# 01_MAIN.net
KiCad netlist of a schematic drawn in Altium Designer
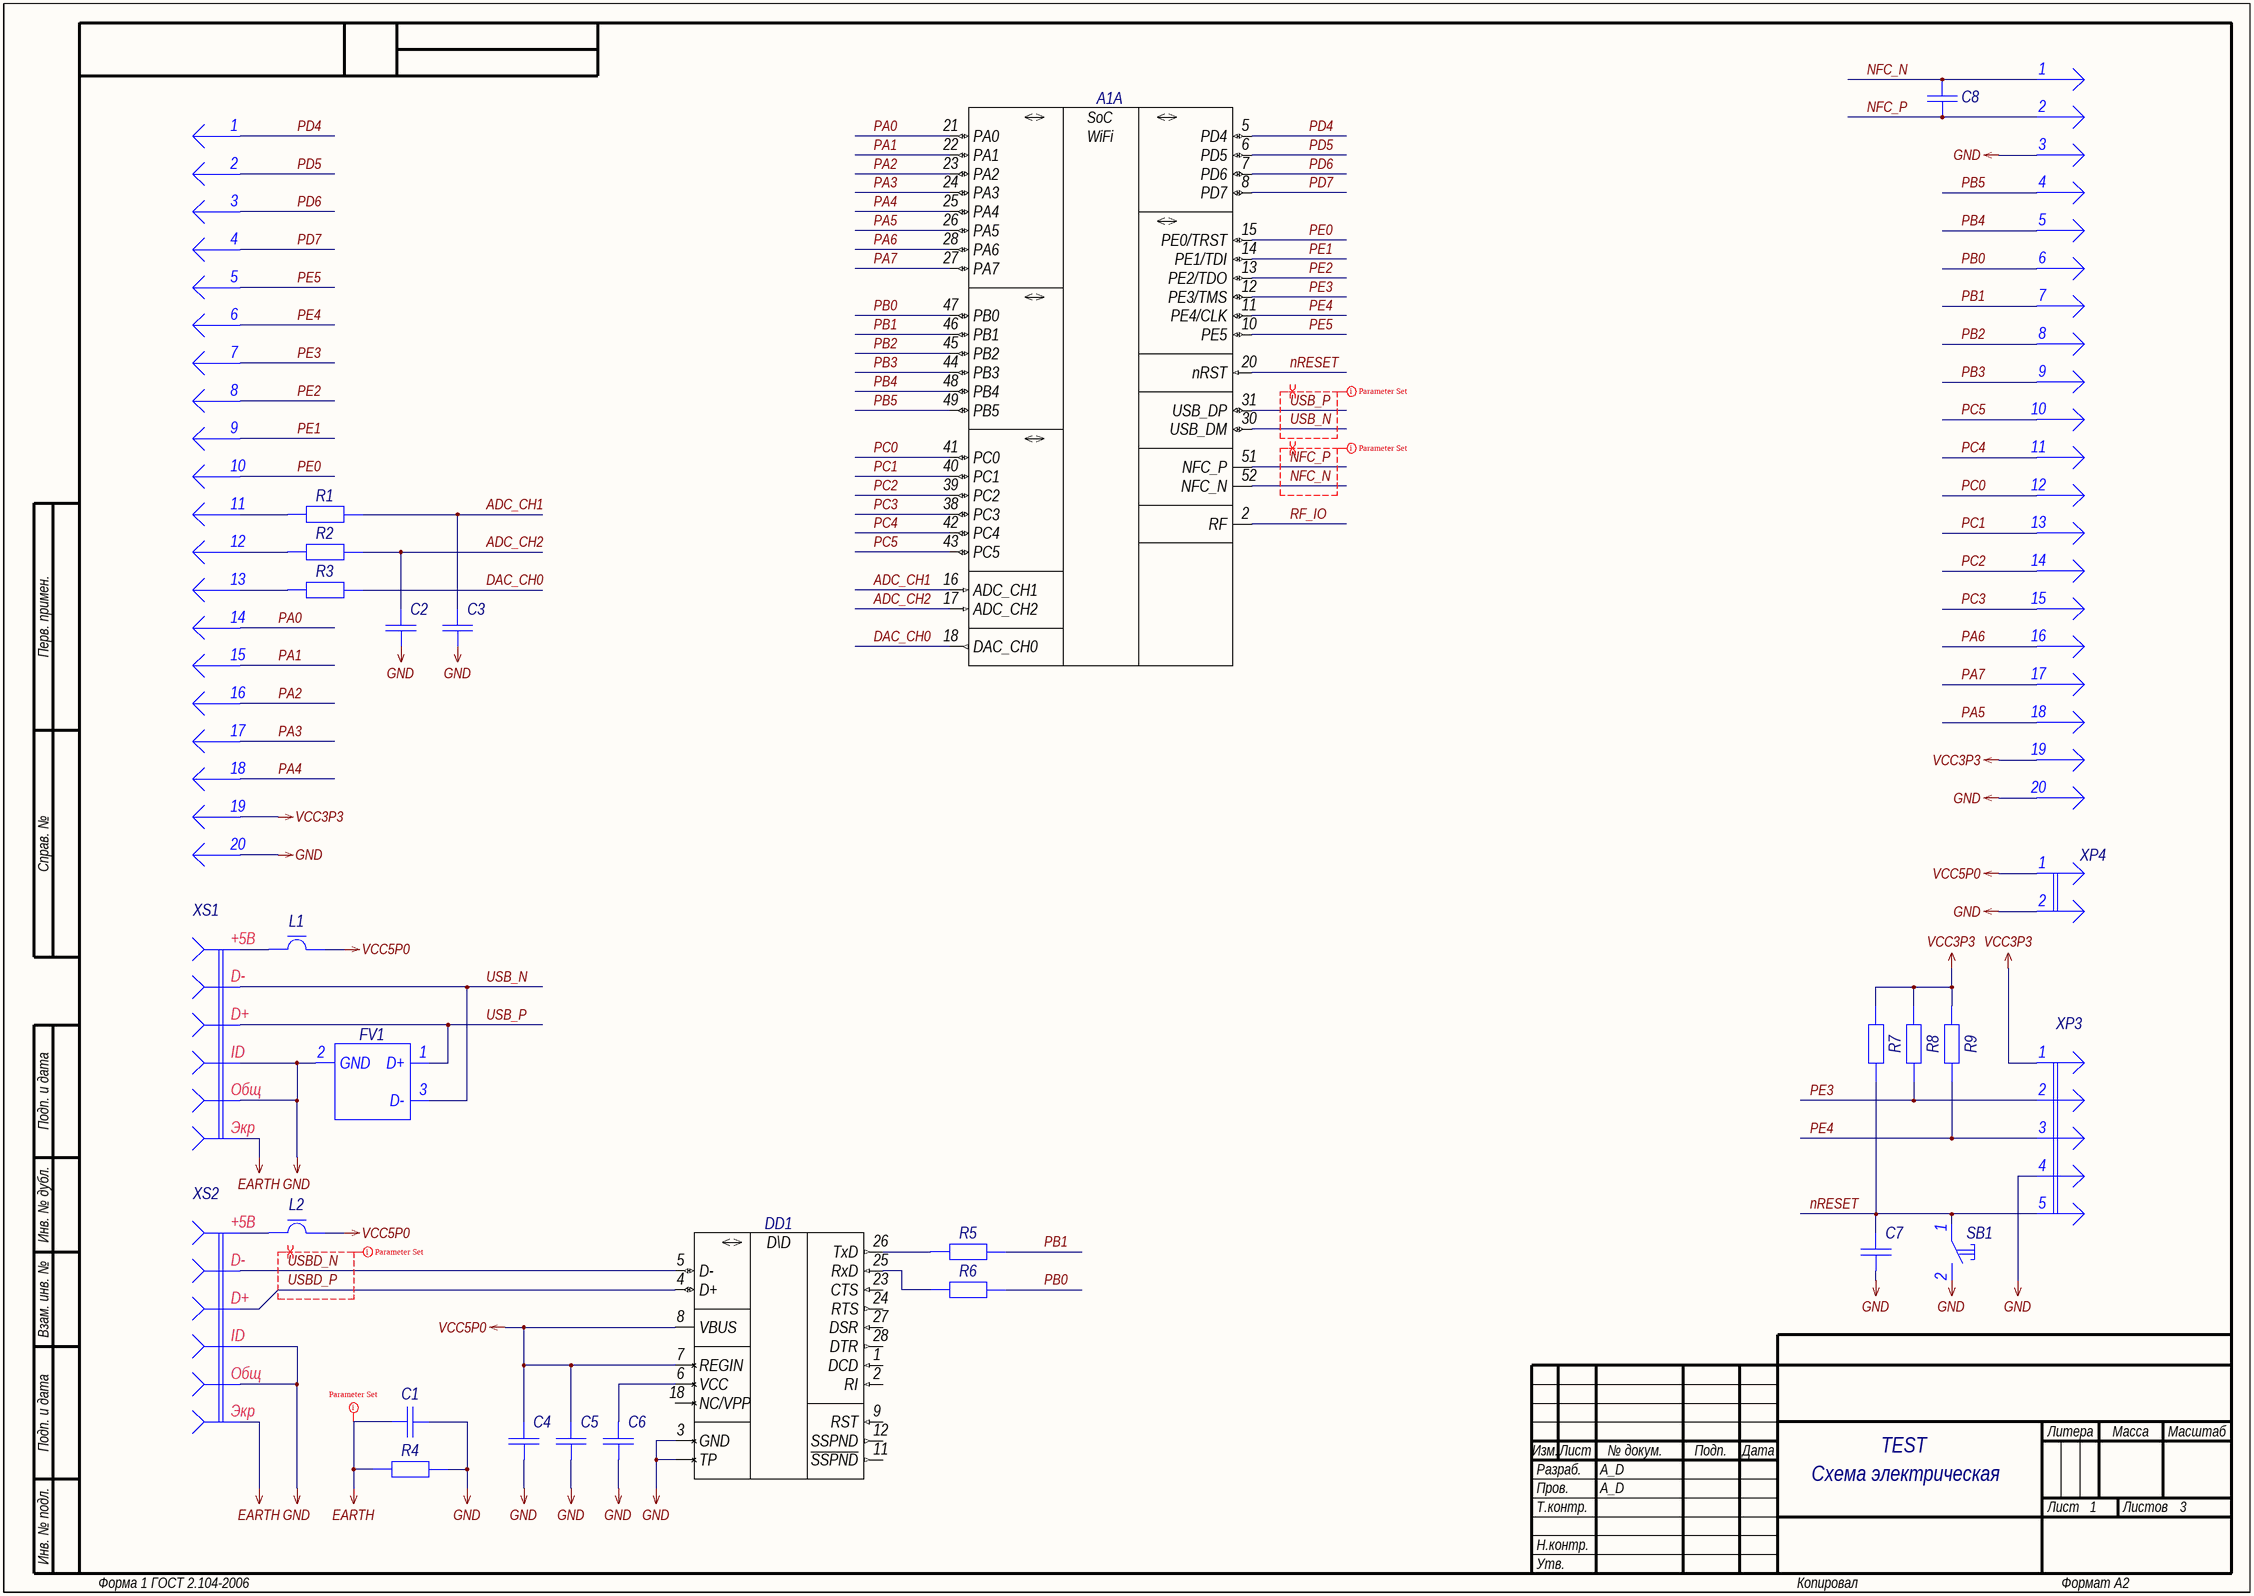
[diagram p0: 01_MAIN.SchDoc]

(export (version "E")
  (design (tool "Eeschema 10.0.6"))
  (components
    (comp (ref "A1")
      (value "AMB-02")
      (footprint "AMB-02")
      (fields
        (field (name "PART NUMBER") "MJIOT-AMB-02")
        (field (name "MANUFACTURER") "MJIOT")
        (field (name "PUBLISHER") "Andrew Danich")
      )
      (libsource (lib "ADLib") (part "AMB-02"))
    )
    (comp (ref "C1")
      (value "Capacitor")
      (footprint "C0603_L")
      (fields
        (field (name "PART NUMBER") "GRM188R72A104KA35D")
        (field (name "VOLTAGE") "100V")
        (field (name "TOLERANCE") "±10%")
        (field (name "PUBLISHER") "Andrew Danich")
      )
      (libsource (lib "ADLib") (part "Capacitor"))
    )
    (comp (ref "C2")
      (value "Capacitor")
      (footprint "C0603_L")
      (fields
        (field (name "PART NUMBER") "GCM1885C2A101JA16D")
        (field (name "VOLTAGE") "100V")
        (field (name "TOLERANCE") "±5%")
        (field (name "PUBLISHER") "Andrew Danich")
      )
      (libsource (lib "ADLib") (part "Capacitor"))
    )
    (comp (ref "C3")
      (value "Capacitor")
      (footprint "C0603_L")
      (fields
        (field (name "PART NUMBER") "GCM1885C2A101JA16D")
        (field (name "VOLTAGE") "100V")
        (field (name "TOLERANCE") "±5%")
        (field (name "PUBLISHER") "Andrew Danich")
      )
      (libsource (lib "ADLib") (part "Capacitor"))
    )
    (comp (ref "C4")
      (value "Capacitor")
      (footprint "C0603_L")
      (fields
        (field (name "PART NUMBER") "GCM188R71E105KA64D")
        (field (name "VOLTAGE") "25V")
        (field (name "TOLERANCE") "±10%")
        (field (name "PUBLISHER") "Andrew Danich")
      )
      (libsource (lib "ADLib") (part "Capacitor"))
    )
    (comp (ref "C5")
      (value "Capacitor")
      (footprint "C0603_L")
      (fields
        (field (name "PART NUMBER") "GRM188R72A104KA35D")
        (field (name "VOLTAGE") "100V")
        (field (name "TOLERANCE") "±10%")
        (field (name "PUBLISHER") "Andrew Danich")
      )
      (libsource (lib "ADLib") (part "Capacitor"))
    )
    (comp (ref "C6")
      (value "Capacitor")
      (footprint "C0603_L")
      (fields
        (field (name "PART NUMBER") "GRM188R72A104KA35D")
        (field (name "VOLTAGE") "100V")
        (field (name "TOLERANCE") "±10%")
        (field (name "PUBLISHER") "Andrew Danich")
      )
      (libsource (lib "ADLib") (part "Capacitor"))
    )
    (comp (ref "C7")
      (value "Capacitor")
      (footprint "C0603_L")
      (fields
        (field (name "PART NUMBER") "GRM188R72A104KA35D")
        (field (name "VOLTAGE") "100V")
        (field (name "TOLERANCE") "±10%")
        (field (name "PUBLISHER") "Andrew Danich")
      )
      (libsource (lib "ADLib") (part "Capacitor"))
    )
    (comp (ref "C8")
      (value "Capacitor")
      (footprint "C0603_L")
      (fields
        (field (name "PART NUMBER") "GRM1885C2A8R2DA01D")
        (field (name "VOLTAGE") "100V")
        (field (name "TOLERANCE") "±0.5pF")
        (field (name "PUBLISHER") "Andrew Danich")
      )
      (libsource (lib "ADLib") (part "Capacitor"))
    )
    (comp (ref "DD1")
      (value "CP2102_9")
      (footprint "QFN-28_050P500X500X100_N")
      (description "Single Chip USB to UART Bridge")
      (fields
        (field (name "PART NUMBER") "CP2102-GM")
        (field (name "MANUFACTURER") "Silicon Labs")
        (field (name "PUBLISHER") "Andrew Danich")
      )
      (libsource (lib "ADLib") (part "CP2102_9"))
    )
    (comp (ref "FV1")
      (value "TPD2EUSB30DRT")
      (footprint "SOT-3_070P100X080X050_N")
      (fields (field (name "MANUFACTURER") "Texas Instruments") (field (name "PUBLISHER") "Andrew Danich"))
      (libsource (lib "ADLib") (part "TPD2EUSB30DRT"))
    )
    (comp (ref "L1")
      (value "FerriteBead")
      (footprint "L0805_L")
      (fields
        (field (name "PART NUMBER") "BLM21PG331SN1")
        (field (name "MANUFACTURER") "Murata")
        (field (name "PUBLISHER") "Andrew Danich")
      )
      (libsource (lib "ADLib") (part "FerriteBead"))
    )
    (comp (ref "L2")
      (value "FerriteBead")
      (footprint "L0805_L")
      (fields
        (field (name "PART NUMBER") "BLM21PG331SN1")
        (field (name "MANUFACTURER") "Murata")
        (field (name "PUBLISHER") "Andrew Danich")
      )
      (libsource (lib "ADLib") (part "FerriteBead"))
    )
    (comp (ref "R1")
      (value "Resistor")
      (footprint "R0603_L")
      (fields
        (field (name "PART NUMBER") "RC0603JR-07100R")
        (field (name "TOLERANCE") "±5%")
        (field (name "MANUFACTURER") "Yageo")
        (field (name "PUBLISHER") "Andrew Danich")
      )
      (libsource (lib "ADLib") (part "Resistor"))
    )
    (comp (ref "R2")
      (value "Resistor")
      (footprint "R0603_L")
      (fields
        (field (name "PART NUMBER") "RC0603JR-07100R")
        (field (name "TOLERANCE") "±5%")
        (field (name "MANUFACTURER") "Yageo")
        (field (name "PUBLISHER") "Andrew Danich")
      )
      (libsource (lib "ADLib") (part "Resistor"))
    )
    (comp (ref "R3")
      (value "Resistor")
      (footprint "R0603_L")
      (fields
        (field (name "PART NUMBER") "RC0603JR-070R")
        (field (name "TOLERANCE") "±5%")
        (field (name "MANUFACTURER") "Yageo")
        (field (name "PUBLISHER") "Andrew Danich")
      )
      (libsource (lib "ADLib") (part "Resistor"))
    )
    (comp (ref "R4")
      (value "Resistor")
      (footprint "R0603_L")
      (fields
        (field (name "PART NUMBER") "RC0603JR-07100KL")
        (field (name "TOLERANCE") "±5%")
        (field (name "MANUFACTURER") "Yageo")
        (field (name "PUBLISHER") "Andrew Danich")
      )
      (libsource (lib "ADLib") (part "Resistor"))
    )
    (comp (ref "R5")
      (value "Resistor")
      (footprint "R0603_L")
      (fields
        (field (name "PART NUMBER") "RC0603JR-071KL")
        (field (name "TOLERANCE") "±5%")
        (field (name "MANUFACTURER") "Yageo")
        (field (name "PUBLISHER") "Andrew Danich")
      )
      (libsource (lib "ADLib") (part "Resistor"))
    )
    (comp (ref "R6")
      (value "Resistor")
      (footprint "R0603_L")
      (fields
        (field (name "PART NUMBER") "RC0603JR-071KL")
        (field (name "TOLERANCE") "±5%")
        (field (name "MANUFACTURER") "Yageo")
        (field (name "PUBLISHER") "Andrew Danich")
      )
      (libsource (lib "ADLib") (part "Resistor"))
    )
    (comp (ref "R7")
      (value "Resistor")
      (footprint "R0603_L")
      (fields
        (field (name "PART NUMBER") "RC0603JR-0710KL")
        (field (name "TOLERANCE") "±5%")
        (field (name "MANUFACTURER") "Yageo")
        (field (name "PUBLISHER") "Andrew Danich")
      )
      (libsource (lib "ADLib") (part "Resistor"))
    )
    (comp (ref "R8")
      (value "Resistor")
      (footprint "R0603_L")
      (fields
        (field (name "PART NUMBER") "RC0603JR-0710KL")
        (field (name "TOLERANCE") "±5%")
        (field (name "MANUFACTURER") "Yageo")
        (field (name "PUBLISHER") "Andrew Danich")
      )
      (libsource (lib "ADLib") (part "Resistor"))
    )
    (comp (ref "R9")
      (value "Resistor")
      (footprint "R0603_L")
      (fields
        (field (name "PART NUMBER") "RC0603JR-0710KL")
        (field (name "TOLERANCE") "±5%")
        (field (name "MANUFACTURER") "Yageo")
        (field (name "PUBLISHER") "Andrew Danich")
      )
      (libsource (lib "ADLib") (part "Resistor"))
    )
    (comp (ref "SB1")
      (value "RESET")
      (footprint "IT-1185AP")
      (fields (field (name "PART NUMBER") "IT-1185AP") (field (name "PUBLISHER") "Andrew Danich"))
      (libsource (lib "ADLib") (part "BT-01x-01p"))
    )
    (comp (ref "XP1")
      (value "Text")
      (footprint "PLS-20")
      (fields (field (name "PART NUMBER") "PLS-20") (field (name "PUBLISHER") "Andrew Danich"))
      (libsource (lib "ADLib") (part "Con-20-M_S"))
    )
    (comp (ref "XP2")
      (value "Text")
      (footprint "PLS-20")
      (fields (field (name "PART NUMBER") "PLS-20") (field (name "PUBLISHER") "Andrew Danich"))
      (libsource (lib "ADLib") (part "Con-20-M_S"))
    )
    (comp (ref "XP3")
      (value "Text")
      (footprint "PLS-5")
      (fields (field (name "PART NUMBER") "PLS-5") (field (name "PUBLISHER") "Andrew Danich"))
      (libsource (lib "ADLib") (part "Con-5-M"))
    )
    (comp (ref "XP4")
      (value "Text")
      (footprint "PLS-2")
      (fields (field (name "PART NUMBER") "PLS-2") (field (name "PUBLISHER") "Andrew Danich"))
      (libsource (lib "ADLib") (part "Con-2-M"))
    )
    (comp (ref "XS1")
      (value "Text")
      (footprint "1981568-1")
      (fields
        (field (name "PART NUMBER") "1981568-1")
        (field (name "MANUFACTURER") "TE Connectivity")
        (field (name "PUBLISHER") "Andrew Danich")
      )
      (libsource (lib "ADLib") (part "Con-6-F-USB"))
    )
    (comp (ref "XS2")
      (value "Text")
      (footprint "1981568-1")
      (fields
        (field (name "PART NUMBER") "1981568-1")
        (field (name "MANUFACTURER") "TE Connectivity")
        (field (name "PUBLISHER") "Andrew Danich")
      )
      (libsource (lib "ADLib") (part "Con-6-F-USB"))
    )
  )
  (nets
    (net (code "1") (name "/ADC_CH1") (class "Default")
      (node (ref "A1") (pin "16") (pinfunction "ADC_CH1_16") (pintype "input"))
      (node (ref "C3") (pin "2") (pinfunction "2_2") (pintype "passive"))
      (node (ref "R1") (pin "2") (pinfunction "2_2") (pintype "passive"))
    )
    (net (code "2") (name "/ADC_CH2") (class "Default")
      (node (ref "A1") (pin "17") (pinfunction "ADC_CH2_17") (pintype "input"))
      (node (ref "C2") (pin "2") (pinfunction "2_2") (pintype "passive"))
      (node (ref "R2") (pin "2") (pinfunction "2_2") (pintype "passive"))
    )
    (net (code "3") (name "/DAC_CH0") (class "Default")
      (node (ref "A1") (pin "18") (pinfunction "DAC_CH0_18") (pintype "output"))
      (node (ref "R3") (pin "2") (pinfunction "2_2") (pintype "passive"))
    )
    (net (code "4") (name "/NFC_N") (class "Default")
      (node (ref "A1") (pin "52") (pinfunction "NFC_N_52") (pintype "passive"))
      (node (ref "C8") (pin "2") (pinfunction "2_2") (pintype "passive"))
      (node (ref "XP2") (pin "1") (pintype "passive"))
    )
    (net (code "5") (name "/NFC_P") (class "Default")
      (node (ref "A1") (pin "51") (pinfunction "NFC_P_51") (pintype "passive"))
      (node (ref "C8") (pin "1") (pinfunction "1_1") (pintype "passive"))
      (node (ref "XP2") (pin "2") (pintype "passive"))
    )
    (net (code "6") (name "/PA0") (class "Default")
      (node (ref "A1") (pin "21") (pinfunction "PA0_21") (pintype "bidirectional"))
      (node (ref "XP1") (pin "14") (pintype "passive"))
    )
    (net (code "7") (name "/PA1") (class "Default")
      (node (ref "A1") (pin "22") (pinfunction "PA1_22") (pintype "bidirectional"))
      (node (ref "XP1") (pin "15") (pintype "passive"))
    )
    (net (code "8") (name "/PA2") (class "Default")
      (node (ref "A1") (pin "23") (pinfunction "PA2_23") (pintype "bidirectional"))
      (node (ref "XP1") (pin "16") (pintype "passive"))
    )
    (net (code "9") (name "/PA3") (class "Default")
      (node (ref "A1") (pin "24") (pinfunction "PA3_24") (pintype "bidirectional"))
      (node (ref "XP1") (pin "17") (pintype "passive"))
    )
    (net (code "10") (name "/PA4") (class "Default")
      (node (ref "A1") (pin "25") (pinfunction "PA4_25") (pintype "bidirectional"))
      (node (ref "XP1") (pin "18") (pintype "passive"))
    )
    (net (code "11") (name "/PA5") (class "Default")
      (node (ref "A1") (pin "26") (pinfunction "PA5_26") (pintype "bidirectional"))
      (node (ref "XP2") (pin "18") (pintype "passive"))
    )
    (net (code "12") (name "/PA6") (class "Default")
      (node (ref "A1") (pin "28") (pinfunction "PA6_28") (pintype "bidirectional"))
      (node (ref "XP2") (pin "16") (pintype "passive"))
    )
    (net (code "13") (name "/PA7") (class "Default")
      (node (ref "A1") (pin "27") (pinfunction "PA7_27") (pintype "bidirectional"))
      (node (ref "XP2") (pin "17") (pintype "passive"))
    )
    (net (code "14") (name "/PB0") (class "Default")
      (node (ref "A1") (pin "47") (pinfunction "PB0_47") (pintype "bidirectional"))
      (node (ref "R6") (pin "2") (pinfunction "2_2") (pintype "passive"))
      (node (ref "XP2") (pin "6") (pintype "passive"))
    )
    (net (code "15") (name "/PB1") (class "Default")
      (node (ref "A1") (pin "46") (pinfunction "PB1_46") (pintype "bidirectional"))
      (node (ref "R5") (pin "2") (pinfunction "2_2") (pintype "passive"))
      (node (ref "XP2") (pin "7") (pintype "passive"))
    )
    (net (code "16") (name "/PB2") (class "Default")
      (node (ref "A1") (pin "45") (pinfunction "PB2_45") (pintype "bidirectional"))
      (node (ref "XP2") (pin "8") (pintype "passive"))
    )
    (net (code "17") (name "/PB3") (class "Default")
      (node (ref "A1") (pin "44") (pinfunction "PB3_44") (pintype "bidirectional"))
      (node (ref "XP2") (pin "9") (pintype "passive"))
    )
    (net (code "18") (name "/PB4") (class "Default")
      (node (ref "A1") (pin "48") (pinfunction "PB4_48") (pintype "bidirectional"))
      (node (ref "XP2") (pin "5") (pintype "passive"))
    )
    (net (code "19") (name "/PB5") (class "Default")
      (node (ref "A1") (pin "49") (pinfunction "PB5_49") (pintype "bidirectional"))
      (node (ref "XP2") (pin "4") (pintype "passive"))
    )
    (net (code "20") (name "/PC0") (class "Default")
      (node (ref "A1") (pin "41") (pinfunction "PC0_41") (pintype "bidirectional"))
      (node (ref "XP2") (pin "12") (pintype "passive"))
    )
    (net (code "21") (name "/PC1") (class "Default")
      (node (ref "A1") (pin "40") (pinfunction "PC1_40") (pintype "bidirectional"))
      (node (ref "XP2") (pin "13") (pintype "passive"))
    )
    (net (code "22") (name "/PC2") (class "Default")
      (node (ref "A1") (pin "39") (pinfunction "PC2_39") (pintype "bidirectional"))
      (node (ref "XP2") (pin "14") (pintype "passive"))
    )
    (net (code "23") (name "/PC3") (class "Default")
      (node (ref "A1") (pin "38") (pinfunction "PC3_38") (pintype "bidirectional"))
      (node (ref "XP2") (pin "15") (pintype "passive"))
    )
    (net (code "24") (name "/PC4") (class "Default")
      (node (ref "A1") (pin "42") (pinfunction "PC4_42") (pintype "bidirectional"))
      (node (ref "XP2") (pin "11") (pintype "passive"))
    )
    (net (code "25") (name "/PC5") (class "Default")
      (node (ref "A1") (pin "43") (pinfunction "PC5_43") (pintype "bidirectional"))
      (node (ref "XP2") (pin "10") (pintype "passive"))
    )
    (net (code "26") (name "/PD4") (class "Default")
      (node (ref "A1") (pin "5") (pinfunction "PD4_5") (pintype "bidirectional"))
      (node (ref "XP1") (pin "1") (pintype "passive"))
    )
    (net (code "27") (name "/PD5") (class "Default")
      (node (ref "A1") (pin "6") (pinfunction "PD5_6") (pintype "bidirectional"))
      (node (ref "XP1") (pin "2") (pintype "passive"))
    )
    (net (code "28") (name "/PD6") (class "Default")
      (node (ref "A1") (pin "7") (pinfunction "PD6_7") (pintype "bidirectional"))
      (node (ref "XP1") (pin "3") (pintype "passive"))
    )
    (net (code "29") (name "/PD7") (class "Default")
      (node (ref "A1") (pin "8") (pinfunction "PD7_8") (pintype "bidirectional"))
      (node (ref "XP1") (pin "4") (pintype "passive"))
    )
    (net (code "30") (name "/PE0") (class "Default")
      (node (ref "A1") (pin "15") (pinfunction "PE0/TRST_15") (pintype "bidirectional"))
      (node (ref "XP1") (pin "10") (pintype "passive"))
    )
    (net (code "31") (name "/PE1") (class "Default")
      (node (ref "A1") (pin "14") (pinfunction "PE1/TDI_14") (pintype "bidirectional"))
      (node (ref "XP1") (pin "9") (pintype "passive"))
    )
    (net (code "32") (name "/PE2") (class "Default")
      (node (ref "A1") (pin "13") (pinfunction "PE2/TDO_13") (pintype "bidirectional"))
      (node (ref "XP1") (pin "8") (pintype "passive"))
    )
    (net (code "33") (name "/PE3") (class "Default")
      (node (ref "A1") (pin "12") (pinfunction "PE3/TMS_12") (pintype "bidirectional"))
      (node (ref "R8") (pin "1") (pinfunction "1_1") (pintype "passive"))
      (node (ref "XP1") (pin "7") (pintype "passive"))
      (node (ref "XP3") (pin "2") (pintype "passive"))
    )
    (net (code "34") (name "/PE4") (class "Default")
      (node (ref "A1") (pin "11") (pinfunction "PE4/CLK_11") (pintype "bidirectional"))
      (node (ref "R9") (pin "1") (pinfunction "1_1") (pintype "passive"))
      (node (ref "XP1") (pin "6") (pintype "passive"))
      (node (ref "XP3") (pin "3") (pintype "passive"))
    )
    (net (code "35") (name "/PE5") (class "Default")
      (node (ref "A1") (pin "10") (pinfunction "PE5_10") (pintype "bidirectional"))
      (node (ref "XP1") (pin "5") (pintype "passive"))
    )
    (net (code "36") (name "/RF_IO") (class "Default")
      (node (ref "A1") (pin "2") (pinfunction "RF_2") (pintype "passive"))
    )
    (net (code "37") (name "/USBD_N") (class "Default")
      (node (ref "DD1") (pin "5") (pinfunction "D-_5") (pintype "bidirectional"))
      (node (ref "XS2") (pin "2") (pintype "passive"))
    )
    (net (code "38") (name "/USBD_P") (class "Default")
      (node (ref "DD1") (pin "4") (pinfunction "D+_4") (pintype "bidirectional"))
      (node (ref "XS2") (pin "3") (pintype "passive"))
    )
    (net (code "39") (name "/USB_N") (class "Default")
      (node (ref "A1") (pin "30") (pinfunction "USB_DM_30") (pintype "bidirectional"))
      (node (ref "FV1") (pin "3") (pinfunction "D-_3") (pintype "passive"))
      (node (ref "XS1") (pin "2") (pintype "passive"))
    )
    (net (code "40") (name "/USB_P") (class "Default")
      (node (ref "A1") (pin "31") (pinfunction "USB_DP_31") (pintype "bidirectional"))
      (node (ref "FV1") (pin "1") (pinfunction "D+_1") (pintype "passive"))
      (node (ref "XS1") (pin "3") (pintype "passive"))
    )
    (net (code "41") (name "/nRESET") (class "Default")
      (node (ref "A1") (pin "20") (pinfunction "nRST_20") (pintype "input"))
      (node (ref "C7") (pin "2") (pinfunction "2_2") (pintype "passive"))
      (node (ref "R7") (pin "1") (pinfunction "1_1") (pintype "passive"))
      (node (ref "SB1") (pin "1") (pintype "passive"))
      (node (ref "XP3") (pin "5") (pintype "passive"))
    )
    (net (code "42") (name "EARTH") (class "Default")
      (node (ref "C1") (pin "2") (pinfunction "2_2") (pintype "passive"))
      (node (ref "R4") (pin "1") (pinfunction "1_1") (pintype "passive"))
      (node (ref "XS1") (pin "6") (pintype "passive"))
      (node (ref "XS2") (pin "6") (pintype "passive"))
    )
    (net (code "43") (name "GND") (class "Default")
      (node (ref "C1") (pin "1") (pinfunction "1_1") (pintype "passive"))
      (node (ref "C2") (pin "1") (pinfunction "1_1") (pintype "passive"))
      (node (ref "C3") (pin "1") (pinfunction "1_1") (pintype "passive"))
      (node (ref "C4") (pin "1") (pinfunction "1_1") (pintype "passive"))
      (node (ref "C5") (pin "1") (pinfunction "1_1") (pintype "passive"))
      (node (ref "C6") (pin "1") (pinfunction "1_1") (pintype "passive"))
      (node (ref "C7") (pin "1") (pinfunction "1_1") (pintype "passive"))
      (node (ref "DD1") (pin "3") (pinfunction "GND_3") (pintype "power_in"))
      (node (ref "DD1") (pin "TP") (pinfunction "TP_TP") (pintype "power_in"))
      (node (ref "FV1") (pin "2") (pinfunction "GND_2") (pintype "passive"))
      (node (ref "R4") (pin "2") (pinfunction "2_2") (pintype "passive"))
      (node (ref "SB1") (pin "2") (pintype "passive"))
      (node (ref "XP1") (pin "20") (pintype "passive"))
      (node (ref "XP2") (pin "20") (pintype "passive"))
      (node (ref "XP2") (pin "3") (pintype "passive"))
      (node (ref "XP3") (pin "4") (pintype "passive"))
      (node (ref "XP4") (pin "2") (pintype "passive"))
      (node (ref "XS1") (pin "4") (pintype "passive"))
      (node (ref "XS1") (pin "5") (pintype "passive"))
      (node (ref "XS2") (pin "4") (pintype "passive"))
      (node (ref "XS2") (pin "5") (pintype "passive"))
    )
    (net (code "44") (name "Net-(DD1-RxD)") (class "Default")
      (node (ref "DD1") (pin "25") (pinfunction "RxD_25") (pintype "input"))
      (node (ref "R6") (pin "1") (pinfunction "1_1") (pintype "passive"))
    )
    (net (code "45") (name "Net-(DD1-TxD)") (class "Default")
      (node (ref "DD1") (pin "26") (pinfunction "TxD_26") (pintype "output"))
      (node (ref "R5") (pin "1") (pinfunction "1_1") (pintype "passive"))
    )
    (net (code "46") (name "Net-(DD1-VCC)") (class "Default")
      (node (ref "C6") (pin "2") (pinfunction "2_2") (pintype "passive"))
      (node (ref "DD1") (pin "6") (pinfunction "VCC_6") (pintype "power_in"))
    )
    (net (code "47") (name "Net-(L1-Pad1)") (class "Default")
      (node (ref "L1") (pin "1") (pinfunction "1_1") (pintype "passive"))
      (node (ref "XS1") (pin "1") (pintype "passive"))
    )
    (net (code "48") (name "Net-(L2-Pad1)") (class "Default")
      (node (ref "L2") (pin "1") (pinfunction "1_1") (pintype "passive"))
      (node (ref "XS2") (pin "1") (pintype "passive"))
    )
    (net (code "49") (name "Net-(R1-Pad1)") (class "Default")
      (node (ref "R1") (pin "1") (pinfunction "1_1") (pintype "passive"))
      (node (ref "XP1") (pin "11") (pintype "passive"))
    )
    (net (code "50") (name "Net-(R2-Pad1)") (class "Default")
      (node (ref "R2") (pin "1") (pinfunction "1_1") (pintype "passive"))
      (node (ref "XP1") (pin "12") (pintype "passive"))
    )
    (net (code "51") (name "Net-(R3-Pad1)") (class "Default")
      (node (ref "R3") (pin "1") (pinfunction "1_1") (pintype "passive"))
      (node (ref "XP1") (pin "13") (pintype "passive"))
    )
    (net (code "52") (name "VCC3P3") (class "Default")
      (node (ref "R7") (pin "2") (pinfunction "2_2") (pintype "passive"))
      (node (ref "R8") (pin "2") (pinfunction "2_2") (pintype "passive"))
      (node (ref "R9") (pin "2") (pinfunction "2_2") (pintype "passive"))
      (node (ref "XP1") (pin "19") (pintype "passive"))
      (node (ref "XP2") (pin "19") (pintype "passive"))
      (node (ref "XP3") (pin "1") (pintype "passive"))
    )
    (net (code "53") (name "VCC5P0") (class "Default")
      (node (ref "C4") (pin "2") (pinfunction "2_2") (pintype "passive"))
      (node (ref "C5") (pin "2") (pinfunction "2_2") (pintype "passive"))
      (node (ref "DD1") (pin "7") (pinfunction "REGIN_7") (pintype "power_in"))
      (node (ref "DD1") (pin "8") (pinfunction "VBUS_8") (pintype "power_in"))
      (node (ref "L1") (pin "2") (pinfunction "2_2") (pintype "passive"))
      (node (ref "L2") (pin "2") (pinfunction "2_2") (pintype "passive"))
      (node (ref "XP4") (pin "1") (pintype "passive"))
    )
    (net (code "54") (name "unconnected-(DD1-CTS-Pad23)") (class "Default")
      (node (ref "DD1") (pin "23") (pinfunction "CTS_23") (pintype "input"))
    )
    (net (code "55") (name "unconnected-(DD1-DCD-Pad1)") (class "Default")
      (node (ref "DD1") (pin "1") (pinfunction "DCD_1") (pintype "input"))
    )
    (net (code "56") (name "unconnected-(DD1-DSR-Pad27)") (class "Default")
      (node (ref "DD1") (pin "27") (pinfunction "DSR_27") (pintype "input"))
    )
    (net (code "57") (name "unconnected-(DD1-DTR-Pad28)") (class "Default")
      (node (ref "DD1") (pin "28") (pinfunction "DTR_28") (pintype "output"))
    )
    (net (code "58") (name "unconnected-(DD1-NC{slash}VPP-Pad18)") (class "Default")
      (node (ref "DD1") (pin "18") (pinfunction "NC/VPP_18") (pintype "power_in"))
    )
    (net (code "59") (name "unconnected-(DD1-RI-Pad2)") (class "Default")
      (node (ref "DD1") (pin "2") (pinfunction "RI_2") (pintype "input"))
    )
    (net (code "60") (name "unconnected-(DD1-RST-Pad9)") (class "Default")
      (node (ref "DD1") (pin "9") (pinfunction "RST_9") (pintype "input"))
    )
    (net (code "61") (name "unconnected-(DD1-RTS-Pad24)") (class "Default")
      (node (ref "DD1") (pin "24") (pinfunction "RTS_24") (pintype "output"))
    )
    (net (code "62") (name "unconnected-(DD1-SSPND-Pad12)") (class "Default")
      (node (ref "DD1") (pin "12") (pinfunction "SSPND_12") (pintype "output"))
    )
    (net (code "63") (name "unconnected-(DD1-~{SSPND}-Pad11)") (class "Default")
      (node (ref "DD1") (pin "11") (pinfunction "~{SSPND}_11") (pintype "output"))
    )
  )
)
